# inputProtection.net
KiCad netlist of a schematic drawn in EAGLE
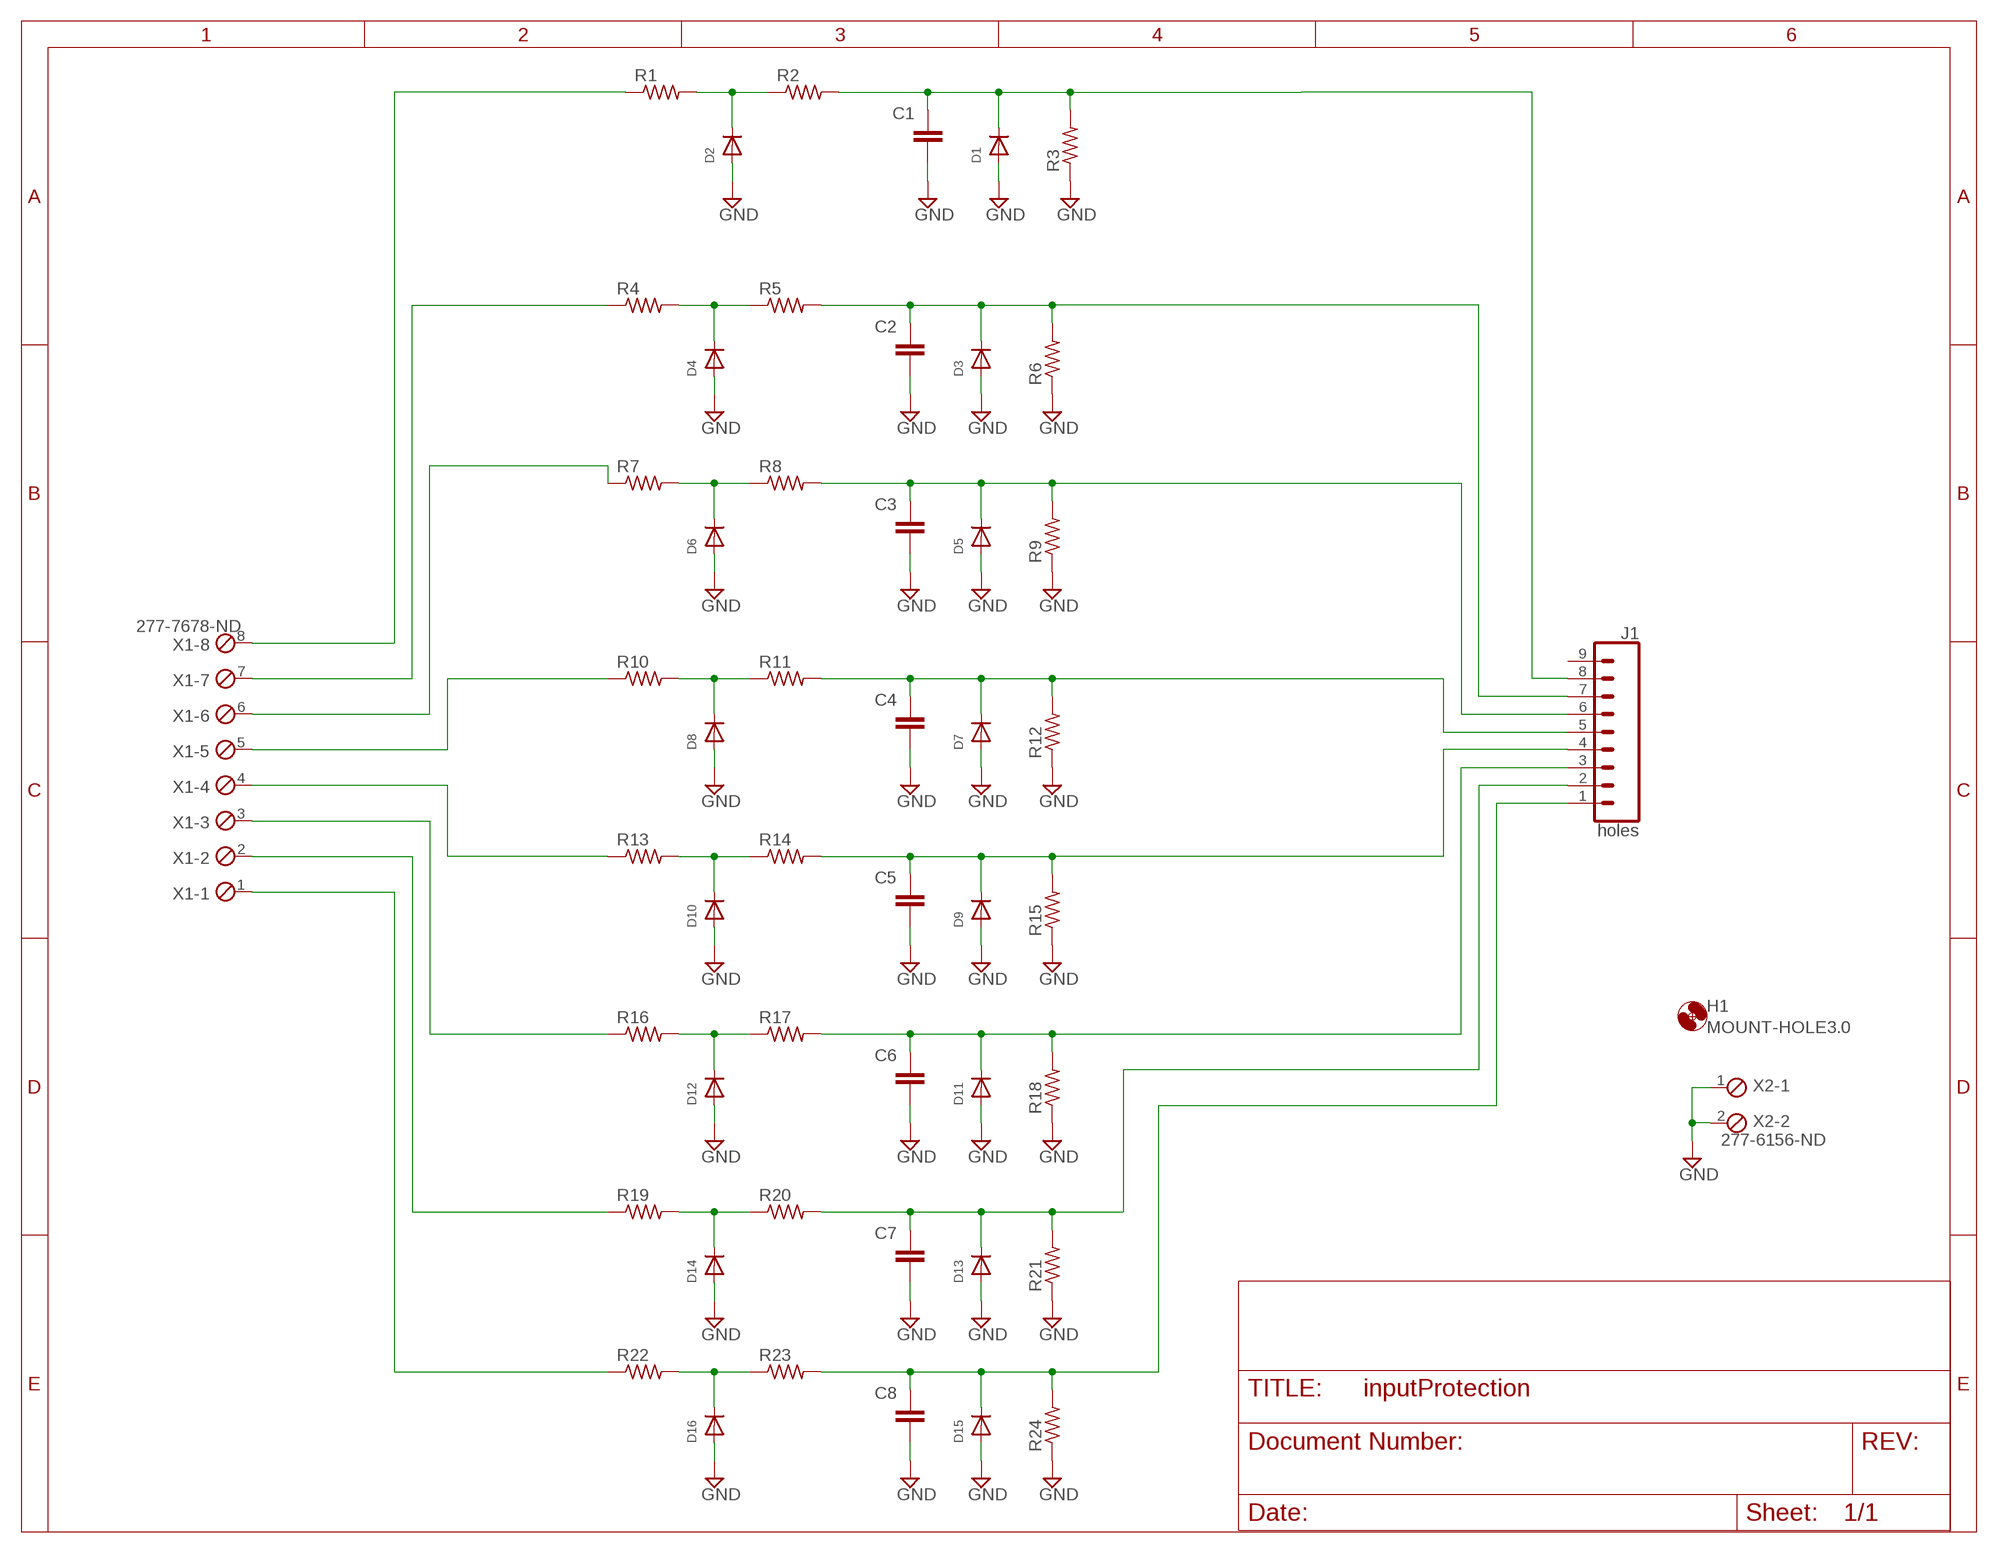
[diagram p0: schematic, sheet 1]

(export (version "E")
  (design (tool "Eeschema 10.0.6"))
  (components
    (comp (ref "C1")
      (value "CC0805KRX7R9BB104")
      (footprint "eagle-import:CAP_0805")
      (fields
        (field (name "DIGIKEY_PART_NUMBER") "311-1140-2-ND")
        (field (name "MANUFACTURER") "Yageo")
        (field (name "DIGIKEY_PART_NUMBER_1") "ECH-U1C103JX5")
        (field (name "MPN") "ECH-U1C103JX5")
        (field (name "CREATED_BY") "PCBLayout.com")
      )
      (libsource (lib "eagle-import") (part "CC0805KRX7R9BB104"))
    )
    (comp (ref "C2")
      (value "CC0805KRX7R9BB104")
      (footprint "eagle-import:CAP_0805")
      (fields
        (field (name "DIGIKEY_PART_NUMBER") "311-1140-2-ND")
        (field (name "MANUFACTURER") "Yageo")
        (field (name "DIGIKEY_PART_NUMBER_1") "ECH-U1C103JX5")
        (field (name "MPN") "ECH-U1C103JX5")
        (field (name "CREATED_BY") "PCBLayout.com")
      )
      (libsource (lib "eagle-import") (part "CC0805KRX7R9BB104"))
    )
    (comp (ref "C3")
      (value "CC0805KRX7R9BB104")
      (footprint "eagle-import:CAP_0805")
      (fields
        (field (name "DIGIKEY_PART_NUMBER") "311-1140-2-ND")
        (field (name "MANUFACTURER") "Yageo")
        (field (name "DIGIKEY_PART_NUMBER_1") "ECH-U1C103JX5")
        (field (name "MPN") "ECH-U1C103JX5")
        (field (name "CREATED_BY") "PCBLayout.com")
      )
      (libsource (lib "eagle-import") (part "CC0805KRX7R9BB104"))
    )
    (comp (ref "C4")
      (value "CC0805KRX7R9BB104")
      (footprint "eagle-import:CAP_0805")
      (fields
        (field (name "DIGIKEY_PART_NUMBER") "311-1140-2-ND")
        (field (name "MANUFACTURER") "Yageo")
        (field (name "DIGIKEY_PART_NUMBER_1") "ECH-U1C103JX5")
        (field (name "MPN") "ECH-U1C103JX5")
        (field (name "CREATED_BY") "PCBLayout.com")
      )
      (libsource (lib "eagle-import") (part "CC0805KRX7R9BB104"))
    )
    (comp (ref "C5")
      (value "CC0805KRX7R9BB104")
      (footprint "eagle-import:CAP_0805")
      (fields
        (field (name "DIGIKEY_PART_NUMBER") "311-1140-2-ND")
        (field (name "MANUFACTURER") "Yageo")
        (field (name "DIGIKEY_PART_NUMBER_1") "ECH-U1C103JX5")
        (field (name "MPN") "ECH-U1C103JX5")
        (field (name "CREATED_BY") "PCBLayout.com")
      )
      (libsource (lib "eagle-import") (part "CC0805KRX7R9BB104"))
    )
    (comp (ref "C6")
      (value "CC0805KRX7R9BB104")
      (footprint "eagle-import:CAP_0805")
      (fields
        (field (name "DIGIKEY_PART_NUMBER") "311-1140-2-ND")
        (field (name "MANUFACTURER") "Yageo")
        (field (name "DIGIKEY_PART_NUMBER_1") "ECH-U1C103JX5")
        (field (name "MPN") "ECH-U1C103JX5")
        (field (name "CREATED_BY") "PCBLayout.com")
      )
      (libsource (lib "eagle-import") (part "CC0805KRX7R9BB104"))
    )
    (comp (ref "C7")
      (value "CC0805KRX7R9BB104")
      (footprint "eagle-import:CAP_0805")
      (fields
        (field (name "DIGIKEY_PART_NUMBER") "311-1140-2-ND")
        (field (name "MANUFACTURER") "Yageo")
        (field (name "DIGIKEY_PART_NUMBER_1") "ECH-U1C103JX5")
        (field (name "MPN") "ECH-U1C103JX5")
        (field (name "CREATED_BY") "PCBLayout.com")
      )
      (libsource (lib "eagle-import") (part "CC0805KRX7R9BB104"))
    )
    (comp (ref "C8")
      (value "CC0805KRX7R9BB104")
      (footprint "eagle-import:CAP_0805")
      (fields
        (field (name "DIGIKEY_PART_NUMBER") "311-1140-2-ND")
        (field (name "MANUFACTURER") "Yageo")
        (field (name "DIGIKEY_PART_NUMBER_1") "ECH-U1C103JX5")
        (field (name "MPN") "ECH-U1C103JX5")
        (field (name "CREATED_BY") "PCBLayout.com")
      )
      (libsource (lib "eagle-import") (part "CC0805KRX7R9BB104"))
    )
    (comp (ref "D1")
      (value "BZT52C4V7-13FDICT-ND")
      (footprint "eagle-import:SOD-123")
      (libsource (lib "eagle-import") (part "DIODESOD-123"))
    )
    (comp (ref "D2")
      (value "BAS70WS_R1_00001")
      (footprint "eagle-import:SOD-323F")
      (libsource (lib "eagle-import") (part "DIODESOD-323F"))
    )
    (comp (ref "D3")
      (value "BZT52C4V7-13FDICT-ND")
      (footprint "eagle-import:SOD-123")
      (libsource (lib "eagle-import") (part "DIODESOD-123"))
    )
    (comp (ref "D4")
      (value "BAS70WS_R1_00001")
      (footprint "eagle-import:SOD-323F")
      (libsource (lib "eagle-import") (part "DIODESOD-323F"))
    )
    (comp (ref "D5")
      (value "BZT52C4V7-13FDICT-ND")
      (footprint "eagle-import:SOD-123")
      (libsource (lib "eagle-import") (part "DIODESOD-123"))
    )
    (comp (ref "D6")
      (value "BAS70WS_R1_00001")
      (footprint "eagle-import:SOD-323F")
      (libsource (lib "eagle-import") (part "DIODESOD-323F"))
    )
    (comp (ref "D7")
      (value "BZT52C4V7-13FDICT-ND")
      (footprint "eagle-import:SOD-123")
      (libsource (lib "eagle-import") (part "DIODESOD-123"))
    )
    (comp (ref "D8")
      (value "BAS70WS_R1_00001")
      (footprint "eagle-import:SOD-323F")
      (libsource (lib "eagle-import") (part "DIODESOD-323F"))
    )
    (comp (ref "D9")
      (value "BZT52C4V7-13FDICT-ND")
      (footprint "eagle-import:SOD-123")
      (libsource (lib "eagle-import") (part "DIODESOD-123"))
    )
    (comp (ref "D10")
      (value "BAS70WS_R1_00001")
      (footprint "eagle-import:SOD-323F")
      (libsource (lib "eagle-import") (part "DIODESOD-323F"))
    )
    (comp (ref "D11")
      (value "BZT52C4V7-13FDICT-ND")
      (footprint "eagle-import:SOD-123")
      (libsource (lib "eagle-import") (part "DIODESOD-123"))
    )
    (comp (ref "D12")
      (value "BAS70WS_R1_00001")
      (footprint "eagle-import:SOD-323F")
      (libsource (lib "eagle-import") (part "DIODESOD-323F"))
    )
    (comp (ref "D13")
      (value "BZT52C4V7-13FDICT-ND")
      (footprint "eagle-import:SOD-123")
      (libsource (lib "eagle-import") (part "DIODESOD-123"))
    )
    (comp (ref "D14")
      (value "BAS70WS_R1_00001")
      (footprint "eagle-import:SOD-323F")
      (libsource (lib "eagle-import") (part "DIODESOD-323F"))
    )
    (comp (ref "D15")
      (value "BZT52C4V7-13FDICT-ND")
      (footprint "eagle-import:SOD-123")
      (libsource (lib "eagle-import") (part "DIODESOD-123"))
    )
    (comp (ref "D16")
      (value "BAS70WS_R1_00001")
      (footprint "eagle-import:SOD-323F")
      (libsource (lib "eagle-import") (part "DIODESOD-323F"))
    )
    (comp (ref "H1")
      (value "MOUNT-HOLE3.0")
      (footprint "eagle-import:3,0")
      (libsource (lib "eagle-import") (part "MOUNT-HOLE3.0"))
    )
    (comp (ref "J1")
      (value "holes")
      (footprint "eagle-import:1X09_LONGPADS")
      (libsource (lib "eagle-import") (part "CONN_09LONGPADS"))
    )
    (comp (ref "R1")
      (value "10 RHM10KCT-ND")
      (footprint "eagle-import:R0805")
      (libsource (lib "eagle-import") (part "R-US_R0805"))
    )
    (comp (ref "R2")
      (value "1k RHM1.0KKCT-ND")
      (footprint "eagle-import:R0805")
      (libsource (lib "eagle-import") (part "R-US_R0805"))
    )
    (comp (ref "R3")
      (value "10k RHM10KKCT-ND")
      (footprint "eagle-import:R0805")
      (libsource (lib "eagle-import") (part "R-US_R0805"))
    )
    (comp (ref "R4")
      (value "10 RHM10KCT-ND")
      (footprint "eagle-import:R0805")
      (libsource (lib "eagle-import") (part "R-US_R0805"))
    )
    (comp (ref "R5")
      (value "1k RHM1.0KKCT-ND")
      (footprint "eagle-import:R0805")
      (libsource (lib "eagle-import") (part "R-US_R0805"))
    )
    (comp (ref "R6")
      (value "10k RHM10KKCT-ND")
      (footprint "eagle-import:R0805")
      (libsource (lib "eagle-import") (part "R-US_R0805"))
    )
    (comp (ref "R7")
      (value "10 RHM10KCT-ND")
      (footprint "eagle-import:R0805")
      (libsource (lib "eagle-import") (part "R-US_R0805"))
    )
    (comp (ref "R8")
      (value "1k RHM1.0KKCT-ND")
      (footprint "eagle-import:R0805")
      (libsource (lib "eagle-import") (part "R-US_R0805"))
    )
    (comp (ref "R9")
      (value "10k RHM10KKCT-ND")
      (footprint "eagle-import:R0805")
      (libsource (lib "eagle-import") (part "R-US_R0805"))
    )
    (comp (ref "R10")
      (value "10 RHM10KCT-ND")
      (footprint "eagle-import:R0805")
      (libsource (lib "eagle-import") (part "R-US_R0805"))
    )
    (comp (ref "R11")
      (value "1k RHM1.0KKCT-ND")
      (footprint "eagle-import:R0805")
      (libsource (lib "eagle-import") (part "R-US_R0805"))
    )
    (comp (ref "R12")
      (value "10k RHM10KKCT-ND")
      (footprint "eagle-import:R0805")
      (libsource (lib "eagle-import") (part "R-US_R0805"))
    )
    (comp (ref "R13")
      (value "10 RHM10KCT-ND")
      (footprint "eagle-import:R0805")
      (libsource (lib "eagle-import") (part "R-US_R0805"))
    )
    (comp (ref "R14")
      (value "1k RHM1.0KKCT-ND")
      (footprint "eagle-import:R0805")
      (libsource (lib "eagle-import") (part "R-US_R0805"))
    )
    (comp (ref "R15")
      (value "10k RHM10KKCT-ND")
      (footprint "eagle-import:R0805")
      (libsource (lib "eagle-import") (part "R-US_R0805"))
    )
    (comp (ref "R16")
      (value "10 RHM10KCT-ND")
      (footprint "eagle-import:R0805")
      (libsource (lib "eagle-import") (part "R-US_R0805"))
    )
    (comp (ref "R17")
      (value "1k RHM1.0KKCT-ND")
      (footprint "eagle-import:R0805")
      (libsource (lib "eagle-import") (part "R-US_R0805"))
    )
    (comp (ref "R18")
      (value "10k RHM10KKCT-ND")
      (footprint "eagle-import:R0805")
      (libsource (lib "eagle-import") (part "R-US_R0805"))
    )
    (comp (ref "R19")
      (value "10 RHM10KCT-ND")
      (footprint "eagle-import:R0805")
      (libsource (lib "eagle-import") (part "R-US_R0805"))
    )
    (comp (ref "R20")
      (value "1k RHM1.0KKCT-ND")
      (footprint "eagle-import:R0805")
      (libsource (lib "eagle-import") (part "R-US_R0805"))
    )
    (comp (ref "R21")
      (value "10k RHM10KKCT-ND")
      (footprint "eagle-import:R0805")
      (libsource (lib "eagle-import") (part "R-US_R0805"))
    )
    (comp (ref "R22")
      (value "10 RHM10KCT-ND")
      (footprint "eagle-import:R0805")
      (libsource (lib "eagle-import") (part "R-US_R0805"))
    )
    (comp (ref "R23")
      (value "1k RHM1.0KKCT-ND")
      (footprint "eagle-import:R0805")
      (libsource (lib "eagle-import") (part "R-US_R0805"))
    )
    (comp (ref "R24")
      (value "10k RHM10KKCT-ND")
      (footprint "eagle-import:R0805")
      (libsource (lib "eagle-import") (part "R-US_R0805"))
    )
    (comp (ref "X1")
      (value "277-7678-ND")
      (footprint "eagle-import:8POL254")
      (libsource (lib "eagle-import") (part "MPT8"))
    )
    (comp (ref "X2")
      (value "277-6156-ND")
      (footprint "eagle-import:2POL254")
      (libsource (lib "eagle-import") (part "MPT2"))
    )
  )
  (nets
    (net (code "1") (name "GND") (class "Default")
      (node (ref "C1") (pin "2") (pinfunction "2_2") (pintype "passive"))
      (node (ref "C2") (pin "2") (pinfunction "2_2") (pintype "passive"))
      (node (ref "C3") (pin "2") (pinfunction "2_2") (pintype "passive"))
      (node (ref "C4") (pin "2") (pinfunction "2_2") (pintype "passive"))
      (node (ref "C5") (pin "2") (pinfunction "2_2") (pintype "passive"))
      (node (ref "C6") (pin "2") (pinfunction "2_2") (pintype "passive"))
      (node (ref "C7") (pin "2") (pinfunction "2_2") (pintype "passive"))
      (node (ref "C8") (pin "2") (pinfunction "2_2") (pintype "passive"))
      (node (ref "D1") (pin "A") (pinfunction "A_A") (pintype "passive"))
      (node (ref "D10") (pin "A") (pinfunction "A_A") (pintype "passive"))
      (node (ref "D11") (pin "A") (pinfunction "A_A") (pintype "passive"))
      (node (ref "D12") (pin "A") (pinfunction "A_A") (pintype "passive"))
      (node (ref "D13") (pin "A") (pinfunction "A_A") (pintype "passive"))
      (node (ref "D14") (pin "A") (pinfunction "A_A") (pintype "passive"))
      (node (ref "D15") (pin "A") (pinfunction "A_A") (pintype "passive"))
      (node (ref "D16") (pin "A") (pinfunction "A_A") (pintype "passive"))
      (node (ref "D2") (pin "A") (pinfunction "A_A") (pintype "passive"))
      (node (ref "D3") (pin "A") (pinfunction "A_A") (pintype "passive"))
      (node (ref "D4") (pin "A") (pinfunction "A_A") (pintype "passive"))
      (node (ref "D5") (pin "A") (pinfunction "A_A") (pintype "passive"))
      (node (ref "D6") (pin "A") (pinfunction "A_A") (pintype "passive"))
      (node (ref "D7") (pin "A") (pinfunction "A_A") (pintype "passive"))
      (node (ref "D8") (pin "A") (pinfunction "A_A") (pintype "passive"))
      (node (ref "D9") (pin "A") (pinfunction "A_A") (pintype "passive"))
      (node (ref "R12") (pin "1") (pinfunction "1_1") (pintype "passive"))
      (node (ref "R15") (pin "1") (pinfunction "1_1") (pintype "passive"))
      (node (ref "R18") (pin "1") (pinfunction "1_1") (pintype "passive"))
      (node (ref "R21") (pin "1") (pinfunction "1_1") (pintype "passive"))
      (node (ref "R24") (pin "1") (pinfunction "1_1") (pintype "passive"))
      (node (ref "R3") (pin "1") (pinfunction "1_1") (pintype "passive"))
      (node (ref "R6") (pin "1") (pinfunction "1_1") (pintype "passive"))
      (node (ref "R9") (pin "1") (pinfunction "1_1") (pintype "passive"))
      (node (ref "X2") (pin "1") (pinfunction "1_1") (pintype "passive"))
      (node (ref "X2") (pin "2") (pinfunction "1_2") (pintype "passive"))
    )
    (net (code "2") (name "Net-(C1-Pad1)") (class "Default")
      (node (ref "C1") (pin "1") (pinfunction "1_1") (pintype "passive"))
      (node (ref "D1") (pin "C") (pinfunction "C_C") (pintype "passive"))
      (node (ref "J1") (pin "8") (pinfunction "8_8") (pintype "passive"))
      (node (ref "R2") (pin "2") (pinfunction "2_2") (pintype "passive"))
      (node (ref "R3") (pin "2") (pinfunction "2_2") (pintype "passive"))
    )
    (net (code "3") (name "Net-(C2-Pad1)") (class "Default")
      (node (ref "C2") (pin "1") (pinfunction "1_1") (pintype "passive"))
      (node (ref "D3") (pin "C") (pinfunction "C_C") (pintype "passive"))
      (node (ref "J1") (pin "7") (pinfunction "7_7") (pintype "passive"))
      (node (ref "R5") (pin "2") (pinfunction "2_2") (pintype "passive"))
      (node (ref "R6") (pin "2") (pinfunction "2_2") (pintype "passive"))
    )
    (net (code "4") (name "Net-(C3-Pad1)") (class "Default")
      (node (ref "C3") (pin "1") (pinfunction "1_1") (pintype "passive"))
      (node (ref "D5") (pin "C") (pinfunction "C_C") (pintype "passive"))
      (node (ref "J1") (pin "6") (pinfunction "6_6") (pintype "passive"))
      (node (ref "R8") (pin "2") (pinfunction "2_2") (pintype "passive"))
      (node (ref "R9") (pin "2") (pinfunction "2_2") (pintype "passive"))
    )
    (net (code "5") (name "Net-(C4-Pad1)") (class "Default")
      (node (ref "C4") (pin "1") (pinfunction "1_1") (pintype "passive"))
      (node (ref "D7") (pin "C") (pinfunction "C_C") (pintype "passive"))
      (node (ref "J1") (pin "5") (pinfunction "5_5") (pintype "passive"))
      (node (ref "R11") (pin "2") (pinfunction "2_2") (pintype "passive"))
      (node (ref "R12") (pin "2") (pinfunction "2_2") (pintype "passive"))
    )
    (net (code "6") (name "Net-(C5-Pad1)") (class "Default")
      (node (ref "C5") (pin "1") (pinfunction "1_1") (pintype "passive"))
      (node (ref "D9") (pin "C") (pinfunction "C_C") (pintype "passive"))
      (node (ref "J1") (pin "4") (pinfunction "4_4") (pintype "passive"))
      (node (ref "R14") (pin "2") (pinfunction "2_2") (pintype "passive"))
      (node (ref "R15") (pin "2") (pinfunction "2_2") (pintype "passive"))
    )
    (net (code "7") (name "Net-(C6-Pad1)") (class "Default")
      (node (ref "C6") (pin "1") (pinfunction "1_1") (pintype "passive"))
      (node (ref "D11") (pin "C") (pinfunction "C_C") (pintype "passive"))
      (node (ref "J1") (pin "3") (pinfunction "3_3") (pintype "passive"))
      (node (ref "R17") (pin "2") (pinfunction "2_2") (pintype "passive"))
      (node (ref "R18") (pin "2") (pinfunction "2_2") (pintype "passive"))
    )
    (net (code "8") (name "Net-(C7-Pad1)") (class "Default")
      (node (ref "C7") (pin "1") (pinfunction "1_1") (pintype "passive"))
      (node (ref "D13") (pin "C") (pinfunction "C_C") (pintype "passive"))
      (node (ref "J1") (pin "2") (pinfunction "2_2") (pintype "passive"))
      (node (ref "R20") (pin "2") (pinfunction "2_2") (pintype "passive"))
      (node (ref "R21") (pin "2") (pinfunction "2_2") (pintype "passive"))
    )
    (net (code "9") (name "Net-(C8-Pad1)") (class "Default")
      (node (ref "C8") (pin "1") (pinfunction "1_1") (pintype "passive"))
      (node (ref "D15") (pin "C") (pinfunction "C_C") (pintype "passive"))
      (node (ref "J1") (pin "1") (pinfunction "1_1") (pintype "passive"))
      (node (ref "R23") (pin "2") (pinfunction "2_2") (pintype "passive"))
      (node (ref "R24") (pin "2") (pinfunction "2_2") (pintype "passive"))
    )
    (net (code "10") (name "Net-(D2-PadC)") (class "Default")
      (node (ref "D2") (pin "C") (pinfunction "C_C") (pintype "passive"))
      (node (ref "R1") (pin "2") (pinfunction "2_2") (pintype "passive"))
      (node (ref "R2") (pin "1") (pinfunction "1_1") (pintype "passive"))
    )
    (net (code "11") (name "Net-(D4-PadC)") (class "Default")
      (node (ref "D4") (pin "C") (pinfunction "C_C") (pintype "passive"))
      (node (ref "R4") (pin "2") (pinfunction "2_2") (pintype "passive"))
      (node (ref "R5") (pin "1") (pinfunction "1_1") (pintype "passive"))
    )
    (net (code "12") (name "Net-(D6-PadC)") (class "Default")
      (node (ref "D6") (pin "C") (pinfunction "C_C") (pintype "passive"))
      (node (ref "R7") (pin "2") (pinfunction "2_2") (pintype "passive"))
      (node (ref "R8") (pin "1") (pinfunction "1_1") (pintype "passive"))
    )
    (net (code "13") (name "Net-(D8-PadC)") (class "Default")
      (node (ref "D8") (pin "C") (pinfunction "C_C") (pintype "passive"))
      (node (ref "R10") (pin "2") (pinfunction "2_2") (pintype "passive"))
      (node (ref "R11") (pin "1") (pinfunction "1_1") (pintype "passive"))
    )
    (net (code "14") (name "Net-(D10-PadC)") (class "Default")
      (node (ref "D10") (pin "C") (pinfunction "C_C") (pintype "passive"))
      (node (ref "R13") (pin "2") (pinfunction "2_2") (pintype "passive"))
      (node (ref "R14") (pin "1") (pinfunction "1_1") (pintype "passive"))
    )
    (net (code "15") (name "Net-(D12-PadC)") (class "Default")
      (node (ref "D12") (pin "C") (pinfunction "C_C") (pintype "passive"))
      (node (ref "R16") (pin "2") (pinfunction "2_2") (pintype "passive"))
      (node (ref "R17") (pin "1") (pinfunction "1_1") (pintype "passive"))
    )
    (net (code "16") (name "Net-(D14-PadC)") (class "Default")
      (node (ref "D14") (pin "C") (pinfunction "C_C") (pintype "passive"))
      (node (ref "R19") (pin "2") (pinfunction "2_2") (pintype "passive"))
      (node (ref "R20") (pin "1") (pinfunction "1_1") (pintype "passive"))
    )
    (net (code "17") (name "Net-(D16-PadC)") (class "Default")
      (node (ref "D16") (pin "C") (pinfunction "C_C") (pintype "passive"))
      (node (ref "R22") (pin "2") (pinfunction "2_2") (pintype "passive"))
      (node (ref "R23") (pin "1") (pinfunction "1_1") (pintype "passive"))
    )
    (net (code "18") (name "Net-(R22-Pad1)") (class "Default")
      (node (ref "R22") (pin "1") (pinfunction "1_1") (pintype "passive"))
      (node (ref "X1") (pin "1") (pinfunction "1_1") (pintype "passive"))
    )
    (net (code "19") (name "Net-(X1B-1)") (class "Default")
      (node (ref "R19") (pin "1") (pinfunction "1_1") (pintype "passive"))
      (node (ref "X1") (pin "2") (pinfunction "1_2") (pintype "passive"))
    )
    (net (code "20") (name "Net-(X1C-1)") (class "Default")
      (node (ref "R16") (pin "1") (pinfunction "1_1") (pintype "passive"))
      (node (ref "X1") (pin "3") (pinfunction "1_3") (pintype "passive"))
    )
    (net (code "21") (name "Net-(X1D-1)") (class "Default")
      (node (ref "R13") (pin "1") (pinfunction "1_1") (pintype "passive"))
      (node (ref "X1") (pin "4") (pinfunction "1_4") (pintype "passive"))
    )
    (net (code "22") (name "Net-(X1E-1)") (class "Default")
      (node (ref "R10") (pin "1") (pinfunction "1_1") (pintype "passive"))
      (node (ref "X1") (pin "5") (pinfunction "1_5") (pintype "passive"))
    )
    (net (code "23") (name "Net-(X1F-1)") (class "Default")
      (node (ref "R7") (pin "1") (pinfunction "1_1") (pintype "passive"))
      (node (ref "X1") (pin "6") (pinfunction "1_6") (pintype "passive"))
    )
    (net (code "24") (name "Net-(X1G-1)") (class "Default")
      (node (ref "R4") (pin "1") (pinfunction "1_1") (pintype "passive"))
      (node (ref "X1") (pin "7") (pinfunction "1_7") (pintype "passive"))
    )
    (net (code "25") (name "Net-(X1H-1)") (class "Default")
      (node (ref "R1") (pin "1") (pinfunction "1_1") (pintype "passive"))
      (node (ref "X1") (pin "8") (pinfunction "1_8") (pintype "passive"))
    )
    (net (code "26") (name "unconnected-(J1-Pad9)") (class "Default")
      (node (ref "J1") (pin "9") (pinfunction "9_9") (pintype "passive"))
    )
  )
)
